# gydrodrive_supply.net
KiCad netlist of a schematic drawn in Altium Designer
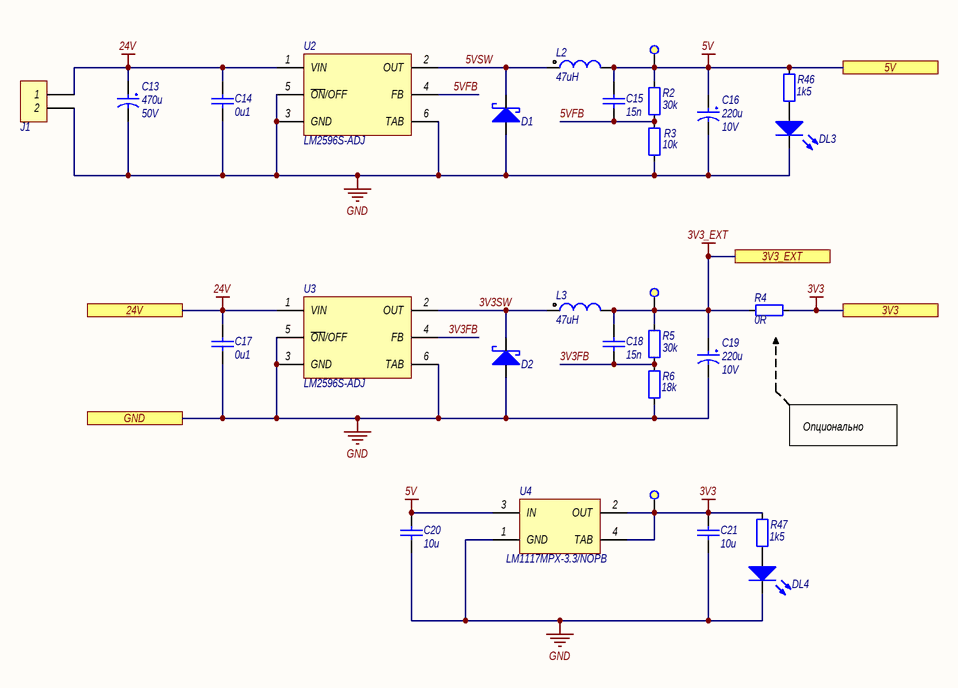
[diagram p0: gydrodrive_supply.SchDoc]

(export (version "E")
  (design (tool "Eeschema 10.0.6"))
  (components
    (comp (ref "C13")
      (value "JRB1H471M05001000200000B")
      (footprint "ECAP1020")
      (description "Конденсатор электролитический")
      (fields (field (name "CAPACITANCE") "470u") (field (name "VOLTAGE") "50V"))
      (libsource (lib "StdLib") (part "CAP_POL"))
    )
    (comp (ref "C14")
      (value "CAP_0805")
      (footprint "CAPC2012-0805M")
      (description "Конденсатор керамический, корпус 0805")
      (fields
        (field (name "CAPACITANCE") "0u1")
        (field (name "PART NUMBER") "CAPC_0805")
        (field (name "VOLTAGE") "50V")
      )
      (libsource (lib "StdLib") (part "CAP"))
    )
    (comp (ref "C15")
      (value "CAP_0805")
      (footprint "CAPC2012-0805M")
      (description "Конденсатор керамический, корпус 0805")
      (fields
        (field (name "CAPACITANCE") "15n")
        (field (name "PART NUMBER") "CAPC_0805")
        (field (name "VOLTAGE") "50V")
      )
      (libsource (lib "StdLib") (part "CAP"))
    )
    (comp (ref "C16")
      (value "JRK1A221M02500630070000B")
      (footprint "ECAP6.37")
      (description "Конденсатор электролитический")
      (fields (field (name "CAPACITANCE") "220u") (field (name "VOLTAGE") "10V"))
      (libsource (lib "StdLib") (part "CAP_POL"))
    )
    (comp (ref "C17")
      (value "CAP_0805")
      (footprint "CAPC2012-0805M")
      (description "Конденсатор керамический, корпус 0805")
      (fields
        (field (name "CAPACITANCE") "0u1")
        (field (name "PART NUMBER") "CAPC_0805")
        (field (name "VOLTAGE") "50V")
      )
      (libsource (lib "StdLib") (part "CAP"))
    )
    (comp (ref "C18")
      (value "CAP_0805")
      (footprint "CAPC2012-0805M")
      (description "Конденсатор керамический, корпус 0805")
      (fields
        (field (name "CAPACITANCE") "15n")
        (field (name "PART NUMBER") "CAPC_0805")
        (field (name "VOLTAGE") "50V")
      )
      (libsource (lib "StdLib") (part "CAP"))
    )
    (comp (ref "C19")
      (value "JRK1A221M02500630070000B")
      (footprint "ECAP6.37")
      (description "Конденсатор электролитический")
      (fields (field (name "CAPACITANCE") "220u") (field (name "VOLTAGE") "10V"))
      (libsource (lib "StdLib") (part "CAP_POL"))
    )
    (comp (ref "C20")
      (value "CAP_0805")
      (footprint "CAPC2012-0805M")
      (description "Конденсатор керамический, корпус 0805")
      (fields
        (field (name "CAPACITANCE") "10u")
        (field (name "PART NUMBER") "CAPC_0805")
        (field (name "VOLTAGE") "16V")
      )
      (libsource (lib "StdLib") (part "CAP"))
    )
    (comp (ref "C21")
      (value "CAP_0805")
      (footprint "CAPC2012-0805M")
      (description "Конденсатор керамический, корпус 0805")
      (fields
        (field (name "CAPACITANCE") "10u")
        (field (name "PART NUMBER") "CAPC_0805")
        (field (name "VOLTAGE") "16V")
      )
      (libsource (lib "StdLib") (part "CAP"))
    )
    (comp (ref "D1")
      (value "SK56")
      (footprint "SMB_M")
      (description "Диод Шоттки")
      (fields (field (name "VOLTAGE") "60V"))
      (libsource (lib "StdLib") (part "SCHOTTKY"))
    )
    (comp (ref "D2")
      (value "SK56")
      (footprint "SMB_M")
      (description "Диод Шоттки")
      (fields (field (name "VOLTAGE") "60V"))
      (libsource (lib "StdLib") (part "SCHOTTKY"))
    )
    (comp (ref "DL3")
      (value "LED_0805")
      (footprint "LEDC2012-0805M")
      (description "Светодиод smd, корпус 0805")
      (libsource (lib "StdLib") (part "LED"))
    )
    (comp (ref "DL4")
      (value "LED_0805")
      (footprint "LEDC2012-0805M")
      (description "Светодиод smd, корпус 0805")
      (libsource (lib "StdLib") (part "LED"))
    )
    (comp (ref "J1")
      (value "DG142V-5.08-02P")
      (footprint "DG142V-5.08-02P")
      (description "Клеммник 2-контактный, шаг 5.08 мм")
      (libsource (lib "StdLib") (part "PIN1x2"))
    )
    (comp (ref "L2")
      (value "IHLP4040DZER470M11")
      (footprint "IND_IHL4040_M")
      (description "Индуктивность силовая")
      (fields (field (name "INDUCTANCE") "47uH"))
      (libsource (lib "StdLib") (part "IND"))
    )
    (comp (ref "L3")
      (value "IHLP4040DZER470M11")
      (footprint "IND_IHL4040_M")
      (description "Индуктивность силовая")
      (fields (field (name "INDUCTANCE") "47uH"))
      (libsource (lib "StdLib") (part "IND"))
    )
    (comp (ref "R2")
      (value "RES_0805")
      (footprint "RESC2012-0805M")
      (description "Рез-р, корпус 0805")
      (fields
        (field (name "RESISTANCE") "30k")
        (field (name "PART NUMBER") "RESC_0805")
        (field (name "TOLERANCE") "5%")
      )
      (libsource (lib "StdLib") (part "RES"))
    )
    (comp (ref "R3")
      (value "RES_0805")
      (footprint "RESC2012-0805M")
      (description "Рез-р, корпус 0805")
      (fields
        (field (name "RESISTANCE") "10k")
        (field (name "PART NUMBER") "RESC_0805")
        (field (name "TOLERANCE") "5%")
      )
      (libsource (lib "StdLib") (part "RES"))
    )
    (comp (ref "R4")
      (value "RES_0805")
      (footprint "RESC2012-0805M")
      (description "Рез-р, корпус 0805")
      (fields
        (field (name "RESISTANCE") "0R")
        (field (name "PART NUMBER") "RESC_0805")
        (field (name "TOLERANCE") "5%")
      )
      (libsource (lib "") (part "RES_1"))
    )
    (comp (ref "R5")
      (value "RES_0805")
      (footprint "RESC2012-0805M")
      (description "Рез-р, корпус 0805")
      (fields
        (field (name "RESISTANCE") "30k")
        (field (name "PART NUMBER") "RESC_0805")
        (field (name "TOLERANCE") "5%")
      )
      (libsource (lib "StdLib") (part "RES"))
    )
    (comp (ref "R6")
      (value "RES_0805")
      (footprint "RESC2012-0805M")
      (description "Рез-р, корпус 0805")
      (fields
        (field (name "RESISTANCE") "18k")
        (field (name "PART NUMBER") "RESC_0805")
        (field (name "TOLERANCE") "5%")
      )
      (libsource (lib "StdLib") (part "RES"))
    )
    (comp (ref "R46")
      (value "RES_0805")
      (footprint "RESC2012-0805M")
      (description "Рез-р, корпус 0805")
      (fields
        (field (name "RESISTANCE") "1k5")
        (field (name "PART NUMBER") "RESC_0805")
        (field (name "TOLERANCE") "5%")
      )
      (libsource (lib "StdLib") (part "RES"))
    )
    (comp (ref "R47")
      (value "RES_0805")
      (footprint "RESC2012-0805M")
      (description "Рез-р, корпус 0805")
      (fields
        (field (name "RESISTANCE") "1k5")
        (field (name "PART NUMBER") "RESC_0805")
        (field (name "TOLERANCE") "5%")
      )
      (libsource (lib "StdLib") (part "RES"))
    )
    (comp (ref "TP2")
      (value "Test point 2")
      (footprint "TP_2")
      (description "Тестовый контакт круглый 2 мм")
      (libsource (lib "StdLib") (part "Test point"))
    )
    (comp (ref "TP3")
      (value "Test point 2")
      (footprint "TP_2")
      (description "Тестовый контакт круглый 2 мм")
      (libsource (lib "StdLib") (part "Test point"))
    )
    (comp (ref "TP4")
      (value "Test point 2")
      (footprint "TP_2")
      (description "Тестовый контакт круглый 2 мм")
      (libsource (lib "StdLib") (part "Test point"))
    )
    (comp (ref "U2")
      (value "LM2596S-ADJ")
      (footprint "TO-263-5M")
      (description "DC-DC преобразователь")
      (libsource (lib "StdLib") (part "LM2596S-ADJ"))
    )
    (comp (ref "U3")
      (value "LM2596S-ADJ")
      (footprint "TO-263-5M")
      (description "DC-DC преобразователь")
      (libsource (lib "StdLib") (part "LM2596S-ADJ"))
    )
    (comp (ref "U4")
      (value "LM1117MPX-3.3/NOPB")
      (footprint "SOT223M")
      (description "Линейный регулятор с низким падением напряжения")
      (libsource (lib "StdLib") (part "LM1117MPX"))
    )
  )
  (nets
    (net (code "1") (name "/3V3FB") (class "Default")
      (node (ref "C18") (pin "2") (pinfunction "2_2") (pintype "passive"))
      (node (ref "R5") (pin "1") (pinfunction "1_1") (pintype "passive"))
      (node (ref "R6") (pin "2") (pinfunction "2_2") (pintype "passive"))
      (node (ref "U3") (pin "4") (pinfunction "FB_4") (pintype "passive"))
    )
    (net (code "2") (name "/3V3SW") (class "Default")
      (node (ref "D2") (pin "1") (pinfunction "K_1") (pintype "passive"))
      (node (ref "L3") (pin "1") (pinfunction "1_1") (pintype "passive"))
      (node (ref "U3") (pin "2") (pinfunction "OUT_2") (pintype "passive"))
    )
    (net (code "3") (name "/5VFB") (class "Default")
      (node (ref "C15") (pin "2") (pinfunction "2_2") (pintype "passive"))
      (node (ref "R2") (pin "1") (pinfunction "1_1") (pintype "passive"))
      (node (ref "R3") (pin "2") (pinfunction "2_2") (pintype "passive"))
      (node (ref "U2") (pin "4") (pinfunction "FB_4") (pintype "passive"))
    )
    (net (code "4") (name "/5VSW") (class "Default")
      (node (ref "D1") (pin "1") (pinfunction "K_1") (pintype "passive"))
      (node (ref "L2") (pin "1") (pinfunction "1_1") (pintype "passive"))
      (node (ref "U2") (pin "2") (pinfunction "OUT_2") (pintype "passive"))
    )
    (net (code "5") (name "3V3") (class "Default")
      (node (ref "C21") (pin "2") (pinfunction "2_2") (pintype "passive"))
      (node (ref "R4") (pin "1") (pinfunction "1_1") (pintype "passive"))
      (node (ref "R47") (pin "2") (pinfunction "2_2") (pintype "passive"))
      (node (ref "TP4") (pin "1") (pinfunction "1_1") (pintype "passive"))
      (node (ref "U4") (pin "2") (pinfunction "OUT_2") (pintype "power_in"))
      (node (ref "U4") (pin "4") (pinfunction "TAB_4") (pintype "power_in"))
    )
    (net (code "6") (name "3V3_EXT") (class "Default")
      (node (ref "C18") (pin "1") (pinfunction "1_1") (pintype "passive"))
      (node (ref "C19") (pin "1") (pinfunction "1_1") (pintype "passive"))
      (node (ref "L3") (pin "2") (pinfunction "2_2") (pintype "passive"))
      (node (ref "R4") (pin "2") (pinfunction "2_2") (pintype "passive"))
      (node (ref "R5") (pin "2") (pinfunction "2_2") (pintype "passive"))
      (node (ref "TP3") (pin "1") (pinfunction "1_1") (pintype "passive"))
    )
    (net (code "7") (name "5V") (class "Default")
      (node (ref "C15") (pin "1") (pinfunction "1_1") (pintype "passive"))
      (node (ref "C16") (pin "1") (pinfunction "1_1") (pintype "passive"))
      (node (ref "C20") (pin "2") (pinfunction "2_2") (pintype "passive"))
      (node (ref "L2") (pin "2") (pinfunction "2_2") (pintype "passive"))
      (node (ref "R2") (pin "2") (pinfunction "2_2") (pintype "passive"))
      (node (ref "R46") (pin "2") (pinfunction "2_2") (pintype "passive"))
      (node (ref "TP2") (pin "1") (pinfunction "1_1") (pintype "passive"))
      (node (ref "U4") (pin "3") (pinfunction "IN_3") (pintype "power_in"))
    )
    (net (code "8") (name "24V") (class "Default")
      (node (ref "C13") (pin "1") (pinfunction "1_1") (pintype "passive"))
      (node (ref "C14") (pin "2") (pinfunction "2_2") (pintype "passive"))
      (node (ref "C17") (pin "2") (pinfunction "2_2") (pintype "passive"))
      (node (ref "J1") (pin "1") (pinfunction "1_1") (pintype "passive"))
      (node (ref "U2") (pin "1") (pinfunction "VIN_1") (pintype "passive"))
      (node (ref "U3") (pin "1") (pinfunction "VIN_1") (pintype "passive"))
    )
    (net (code "9") (name "GND") (class "Default")
      (node (ref "C13") (pin "2") (pinfunction "2_2") (pintype "passive"))
      (node (ref "C14") (pin "1") (pinfunction "1_1") (pintype "passive"))
      (node (ref "C16") (pin "2") (pinfunction "2_2") (pintype "passive"))
      (node (ref "C17") (pin "1") (pinfunction "1_1") (pintype "passive"))
      (node (ref "C19") (pin "2") (pinfunction "2_2") (pintype "passive"))
      (node (ref "C20") (pin "1") (pinfunction "1_1") (pintype "passive"))
      (node (ref "C21") (pin "1") (pinfunction "1_1") (pintype "passive"))
      (node (ref "D1") (pin "2") (pinfunction "A_2") (pintype "passive"))
      (node (ref "D2") (pin "2") (pinfunction "A_2") (pintype "passive"))
      (node (ref "DL3") (pin "1") (pinfunction "K_1") (pintype "passive"))
      (node (ref "DL4") (pin "1") (pinfunction "K_1") (pintype "passive"))
      (node (ref "J1") (pin "2") (pinfunction "2_2") (pintype "passive"))
      (node (ref "R3") (pin "1") (pinfunction "1_1") (pintype "passive"))
      (node (ref "R6") (pin "1") (pinfunction "1_1") (pintype "passive"))
      (node (ref "U2") (pin "3") (pinfunction "GND_3") (pintype "passive"))
      (node (ref "U2") (pin "5") (pinfunction "~{ON}/OFF_5") (pintype "passive"))
      (node (ref "U2") (pin "6") (pinfunction "TAB_6") (pintype "passive"))
      (node (ref "U3") (pin "3") (pinfunction "GND_3") (pintype "passive"))
      (node (ref "U3") (pin "5") (pinfunction "~{ON}/OFF_5") (pintype "passive"))
      (node (ref "U3") (pin "6") (pinfunction "TAB_6") (pintype "passive"))
      (node (ref "U4") (pin "1") (pinfunction "GND_1") (pintype "power_in"))
    )
    (net (code "10") (name "Net-(DL3-A)") (class "Default")
      (node (ref "DL3") (pin "2") (pinfunction "A_2") (pintype "passive"))
      (node (ref "R46") (pin "1") (pinfunction "1_1") (pintype "passive"))
    )
    (net (code "11") (name "Net-(DL4-A)") (class "Default")
      (node (ref "DL4") (pin "2") (pinfunction "A_2") (pintype "passive"))
      (node (ref "R47") (pin "1") (pinfunction "1_1") (pintype "passive"))
    )
  )
)
